# BackplaneConnector.net
KiCad netlist of a schematic drawn in Altium Designer
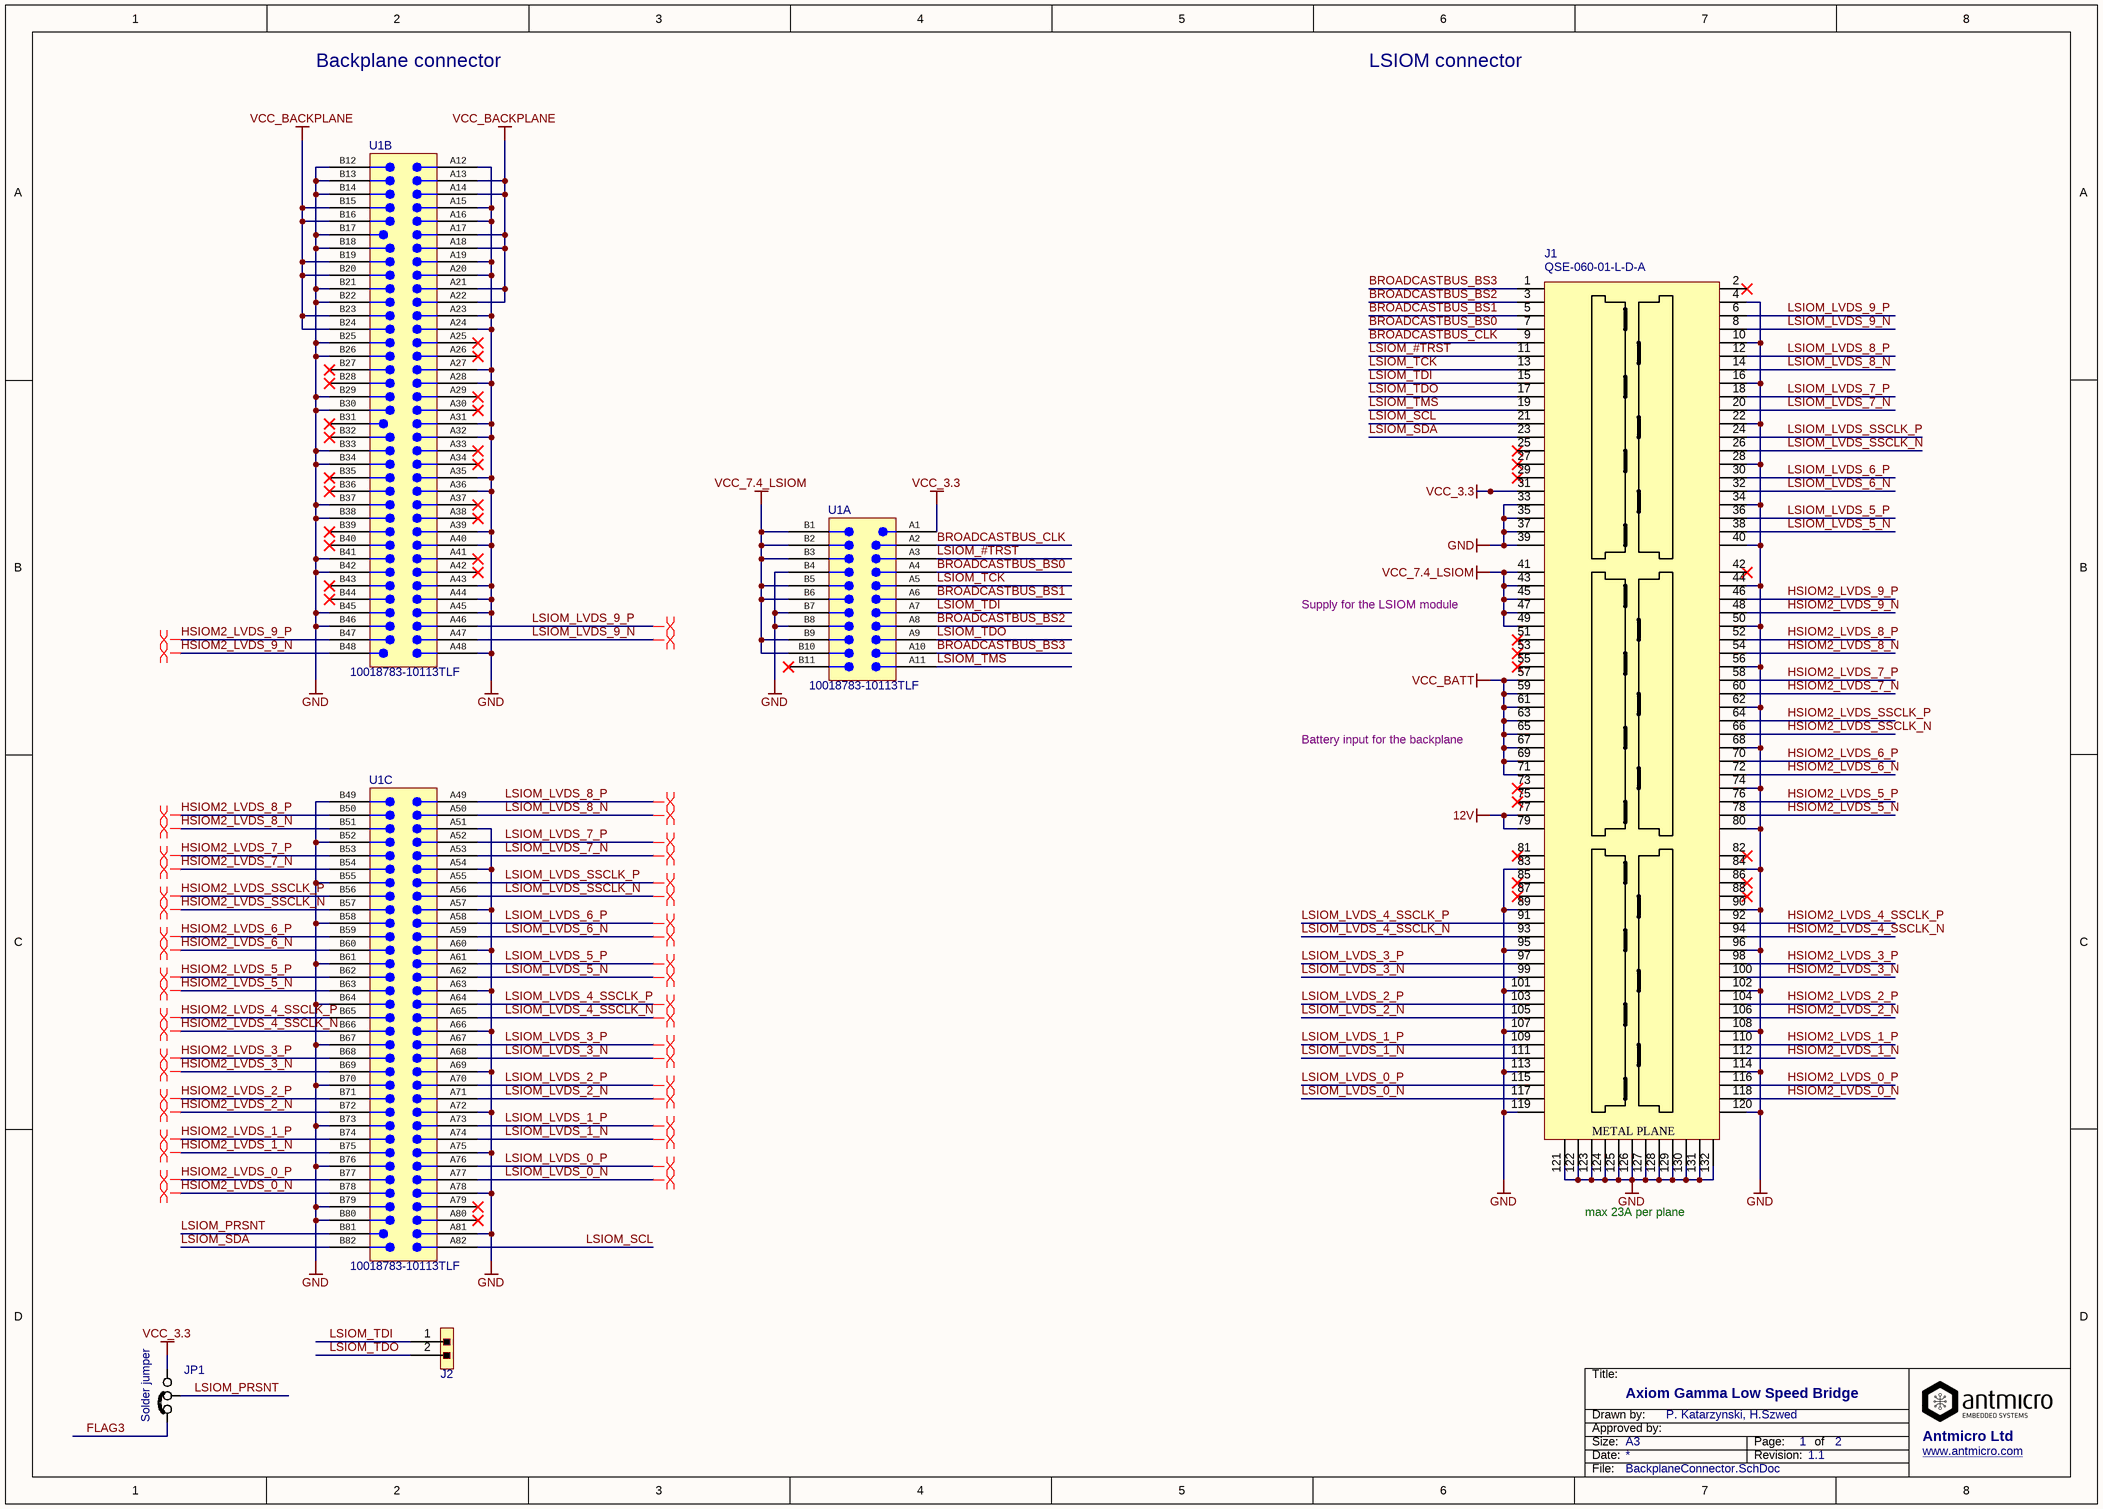
[diagram p0: BackplaneConnector.SchDoc]

(export (version "E")
  (design (tool "Eeschema 10.0.6"))
  (components
    (comp (ref "J1")
      (value "QSE-060-01-L-D-A")
      (footprint "QSE-060-01-L-D-A")
      (fields (field (name "MANUFACTURER") "SAMTEC"))
      (libsource (lib "Axiom_Gamma_LSB") (part "QSE-060-01-L-D-A"))
    )
    (comp (ref "J2")
      (value "1x2 pinhead 2.54mm male")
      (footprint "HEADER_1X2_male 2.54mm Angle")
      (description "1x2 pinhead male angle")
      (fields (field (name "PART NUMBER") "HEADER_1X2_male_angle") (field (name "MANUFACTURER") "MULTICOMP"))
      (libsource (lib "Axiom_Gamma_LSB") (part "HEADER_1X2_male_angle"))
    )
    (comp (ref "JP1")
      (value "Solder jumper")
      (footprint "JUMPER_2WAY")
      (libsource (lib "Axiom_Gamma_LSB") (part "JUMPER_2WAY"))
    )
    (comp (ref "U1")
      (value "10018783-10113TLF")
      (footprint "10018783-10113TLF")
      (description "PCI Express x16 164 2.36 mm")
      (fields (field (name "MANUFACTURER") "AMPHENOL"))
      (libsource (lib "Axiom_Gamma_LSB") (part "10018783-10113TLF"))
    )
  )
  (nets
    (net (code "1") (name "/BROADCASTBUS_BS0") (class "Default")
      (node (ref "J1") (pin "7") (pinfunction "7_7") (pintype "passive"))
      (node (ref "U1") (pin "A4") (pinfunction "A4_A4") (pintype "passive"))
    )
    (net (code "2") (name "/BROADCASTBUS_BS1") (class "Default")
      (node (ref "J1") (pin "5") (pinfunction "5_5") (pintype "passive"))
      (node (ref "U1") (pin "A6") (pinfunction "A6_A6") (pintype "passive"))
    )
    (net (code "3") (name "/BROADCASTBUS_BS2") (class "Default")
      (node (ref "J1") (pin "3") (pinfunction "3_3") (pintype "passive"))
      (node (ref "U1") (pin "A8") (pinfunction "A8_A8") (pintype "passive"))
    )
    (net (code "4") (name "/BROADCASTBUS_BS3") (class "Default")
      (node (ref "J1") (pin "1") (pinfunction "1_1") (pintype "passive"))
      (node (ref "U1") (pin "A10") (pinfunction "A10_A10") (pintype "passive"))
    )
    (net (code "5") (name "/BROADCASTBUS_CLK") (class "Default")
      (node (ref "J1") (pin "9") (pinfunction "9_9") (pintype "passive"))
      (node (ref "U1") (pin "A2") (pinfunction "A2_A2") (pintype "passive"))
    )
    (net (code "6") (name "/FLAG3") (class "Default")
      (node (ref "JP1") (pin "1") (pinfunction "1_1") (pintype "passive"))
    )
    (net (code "7") (name "/HSIOM2_LVDS_0_N") (class "Default")
      (node (ref "J1") (pin "118") (pinfunction "118_118") (pintype "passive"))
      (node (ref "U1") (pin "B78") (pinfunction "B78_B78") (pintype "passive"))
    )
    (net (code "8") (name "/HSIOM2_LVDS_0_P") (class "Default")
      (node (ref "J1") (pin "116") (pinfunction "116_116") (pintype "passive"))
      (node (ref "U1") (pin "B77") (pinfunction "B77_B77") (pintype "passive"))
    )
    (net (code "9") (name "/HSIOM2_LVDS_1_N") (class "Default")
      (node (ref "J1") (pin "112") (pinfunction "112_112") (pintype "passive"))
      (node (ref "U1") (pin "B75") (pinfunction "B75_B75") (pintype "passive"))
    )
    (net (code "10") (name "/HSIOM2_LVDS_1_P") (class "Default")
      (node (ref "J1") (pin "110") (pinfunction "110_110") (pintype "passive"))
      (node (ref "U1") (pin "B74") (pinfunction "B74_B74") (pintype "passive"))
    )
    (net (code "11") (name "/HSIOM2_LVDS_2_N") (class "Default")
      (node (ref "J1") (pin "106") (pinfunction "106_106") (pintype "passive"))
      (node (ref "U1") (pin "B72") (pinfunction "B72_B72") (pintype "passive"))
    )
    (net (code "12") (name "/HSIOM2_LVDS_2_P") (class "Default")
      (node (ref "J1") (pin "104") (pinfunction "104_104") (pintype "passive"))
      (node (ref "U1") (pin "B71") (pinfunction "B71_B71") (pintype "passive"))
    )
    (net (code "13") (name "/HSIOM2_LVDS_3_N") (class "Default")
      (node (ref "J1") (pin "100") (pinfunction "100_100") (pintype "passive"))
      (node (ref "U1") (pin "B69") (pinfunction "B69_B69") (pintype "passive"))
    )
    (net (code "14") (name "/HSIOM2_LVDS_3_P") (class "Default")
      (node (ref "J1") (pin "98") (pinfunction "98_98") (pintype "passive"))
      (node (ref "U1") (pin "B68") (pinfunction "B68_B68") (pintype "passive"))
    )
    (net (code "15") (name "/HSIOM2_LVDS_4_SSCLK_N") (class "Default")
      (node (ref "J1") (pin "94") (pinfunction "94_94") (pintype "passive"))
      (node (ref "U1") (pin "B66") (pinfunction "B66_B66") (pintype "passive"))
    )
    (net (code "16") (name "/HSIOM2_LVDS_4_SSCLK_P") (class "Default")
      (node (ref "J1") (pin "92") (pinfunction "92_92") (pintype "passive"))
      (node (ref "U1") (pin "B65") (pinfunction "B65_B65") (pintype "passive"))
    )
    (net (code "17") (name "/HSIOM2_LVDS_5_N") (class "Default")
      (node (ref "J1") (pin "78") (pinfunction "78_78") (pintype "passive"))
      (node (ref "U1") (pin "B63") (pinfunction "B63_B63") (pintype "passive"))
    )
    (net (code "18") (name "/HSIOM2_LVDS_5_P") (class "Default")
      (node (ref "J1") (pin "76") (pinfunction "76_76") (pintype "passive"))
      (node (ref "U1") (pin "B62") (pinfunction "B62_B62") (pintype "passive"))
    )
    (net (code "19") (name "/HSIOM2_LVDS_6_N") (class "Default")
      (node (ref "J1") (pin "72") (pinfunction "72_72") (pintype "passive"))
      (node (ref "U1") (pin "B60") (pinfunction "B60_B60") (pintype "passive"))
    )
    (net (code "20") (name "/HSIOM2_LVDS_6_P") (class "Default")
      (node (ref "J1") (pin "70") (pinfunction "70_70") (pintype "passive"))
      (node (ref "U1") (pin "B59") (pinfunction "B59_B59") (pintype "passive"))
    )
    (net (code "21") (name "/HSIOM2_LVDS_7_N") (class "Default")
      (node (ref "J1") (pin "60") (pinfunction "60_60") (pintype "passive"))
      (node (ref "U1") (pin "B54") (pinfunction "B54_B54") (pintype "passive"))
    )
    (net (code "22") (name "/HSIOM2_LVDS_7_P") (class "Default")
      (node (ref "J1") (pin "58") (pinfunction "58_58") (pintype "passive"))
      (node (ref "U1") (pin "B53") (pinfunction "B53_B53") (pintype "passive"))
    )
    (net (code "23") (name "/HSIOM2_LVDS_8_N") (class "Default")
      (node (ref "J1") (pin "54") (pinfunction "54_54") (pintype "passive"))
      (node (ref "U1") (pin "B51") (pinfunction "B51_B51") (pintype "passive"))
    )
    (net (code "24") (name "/HSIOM2_LVDS_8_P") (class "Default")
      (node (ref "J1") (pin "52") (pinfunction "52_52") (pintype "passive"))
      (node (ref "U1") (pin "B50") (pinfunction "B50_B50") (pintype "passive"))
    )
    (net (code "25") (name "/HSIOM2_LVDS_9_N") (class "Default")
      (node (ref "J1") (pin "48") (pinfunction "48_48") (pintype "passive"))
      (node (ref "U1") (pin "B48") (pinfunction "B48_B48") (pintype "passive"))
    )
    (net (code "26") (name "/HSIOM2_LVDS_9_P") (class "Default")
      (node (ref "J1") (pin "46") (pinfunction "46_46") (pintype "passive"))
      (node (ref "U1") (pin "B47") (pinfunction "B47_B47") (pintype "passive"))
    )
    (net (code "27") (name "/HSIOM2_LVDS_SSCLK_N") (class "Default")
      (node (ref "J1") (pin "66") (pinfunction "66_66") (pintype "passive"))
      (node (ref "U1") (pin "B57") (pinfunction "B57_B57") (pintype "passive"))
    )
    (net (code "28") (name "/HSIOM2_LVDS_SSCLK_P") (class "Default")
      (node (ref "J1") (pin "64") (pinfunction "64_64") (pintype "passive"))
      (node (ref "U1") (pin "B56") (pinfunction "B56_B56") (pintype "passive"))
    )
    (net (code "29") (name "/LSIOM_#TRST") (class "Default")
      (node (ref "J1") (pin "11") (pinfunction "11_11") (pintype "passive"))
      (node (ref "U1") (pin "A3") (pinfunction "A3_A3") (pintype "passive"))
    )
    (net (code "30") (name "/LSIOM_LVDS_0_N") (class "Default")
      (node (ref "J1") (pin "117") (pinfunction "117_117") (pintype "passive"))
      (node (ref "U1") (pin "A77") (pinfunction "A77_A77") (pintype "passive"))
    )
    (net (code "31") (name "/LSIOM_LVDS_0_P") (class "Default")
      (node (ref "J1") (pin "115") (pinfunction "115_115") (pintype "passive"))
      (node (ref "U1") (pin "A76") (pinfunction "A76_A76") (pintype "passive"))
    )
    (net (code "32") (name "/LSIOM_LVDS_1_N") (class "Default")
      (node (ref "J1") (pin "111") (pinfunction "111_111") (pintype "passive"))
      (node (ref "U1") (pin "A74") (pinfunction "A74_A74") (pintype "passive"))
    )
    (net (code "33") (name "/LSIOM_LVDS_1_P") (class "Default")
      (node (ref "J1") (pin "109") (pinfunction "109_109") (pintype "passive"))
      (node (ref "U1") (pin "A73") (pinfunction "A73_A73") (pintype "passive"))
    )
    (net (code "34") (name "/LSIOM_LVDS_2_N") (class "Default")
      (node (ref "J1") (pin "105") (pinfunction "105_105") (pintype "passive"))
      (node (ref "U1") (pin "A71") (pinfunction "A71_A71") (pintype "passive"))
    )
    (net (code "35") (name "/LSIOM_LVDS_2_P") (class "Default")
      (node (ref "J1") (pin "103") (pinfunction "103_103") (pintype "passive"))
      (node (ref "U1") (pin "A70") (pinfunction "A70_A70") (pintype "passive"))
    )
    (net (code "36") (name "/LSIOM_LVDS_3_N") (class "Default")
      (node (ref "J1") (pin "99") (pinfunction "99_99") (pintype "passive"))
      (node (ref "U1") (pin "A68") (pinfunction "A68_A68") (pintype "passive"))
    )
    (net (code "37") (name "/LSIOM_LVDS_3_P") (class "Default")
      (node (ref "J1") (pin "97") (pinfunction "97_97") (pintype "passive"))
      (node (ref "U1") (pin "A67") (pinfunction "A67_A67") (pintype "passive"))
    )
    (net (code "38") (name "/LSIOM_LVDS_4_SSCLK_N") (class "Default")
      (node (ref "J1") (pin "93") (pinfunction "93_93") (pintype "passive"))
      (node (ref "U1") (pin "A65") (pinfunction "A65_A65") (pintype "passive"))
    )
    (net (code "39") (name "/LSIOM_LVDS_4_SSCLK_P") (class "Default")
      (node (ref "J1") (pin "91") (pinfunction "91_91") (pintype "passive"))
      (node (ref "U1") (pin "A64") (pinfunction "A64_A64") (pintype "passive"))
    )
    (net (code "40") (name "/LSIOM_LVDS_5_N") (class "Default")
      (node (ref "J1") (pin "38") (pinfunction "38_38") (pintype "passive"))
      (node (ref "U1") (pin "A62") (pinfunction "A62_A62") (pintype "passive"))
    )
    (net (code "41") (name "/LSIOM_LVDS_5_P") (class "Default")
      (node (ref "J1") (pin "36") (pinfunction "36_36") (pintype "passive"))
      (node (ref "U1") (pin "A61") (pinfunction "A61_A61") (pintype "passive"))
    )
    (net (code "42") (name "/LSIOM_LVDS_6_N") (class "Default")
      (node (ref "J1") (pin "32") (pinfunction "32_32") (pintype "passive"))
      (node (ref "U1") (pin "A59") (pinfunction "A59_A59") (pintype "passive"))
    )
    (net (code "43") (name "/LSIOM_LVDS_6_P") (class "Default")
      (node (ref "J1") (pin "30") (pinfunction "30_30") (pintype "passive"))
      (node (ref "U1") (pin "A58") (pinfunction "A58_A58") (pintype "passive"))
    )
    (net (code "44") (name "/LSIOM_LVDS_7_N") (class "Default")
      (node (ref "J1") (pin "20") (pinfunction "20_20") (pintype "passive"))
      (node (ref "U1") (pin "A53") (pinfunction "A53_A53") (pintype "passive"))
    )
    (net (code "45") (name "/LSIOM_LVDS_7_P") (class "Default")
      (node (ref "J1") (pin "18") (pinfunction "18_18") (pintype "passive"))
      (node (ref "U1") (pin "A52") (pinfunction "A52_A52") (pintype "passive"))
    )
    (net (code "46") (name "/LSIOM_LVDS_8_N") (class "Default")
      (node (ref "J1") (pin "14") (pinfunction "14_14") (pintype "passive"))
      (node (ref "U1") (pin "A50") (pinfunction "A50_A50") (pintype "passive"))
    )
    (net (code "47") (name "/LSIOM_LVDS_8_P") (class "Default")
      (node (ref "J1") (pin "12") (pinfunction "12_12") (pintype "passive"))
      (node (ref "U1") (pin "A49") (pinfunction "A49_A49") (pintype "passive"))
    )
    (net (code "48") (name "/LSIOM_LVDS_9_N") (class "Default")
      (node (ref "J1") (pin "8") (pinfunction "8_8") (pintype "passive"))
      (node (ref "U1") (pin "A47") (pinfunction "A47_A47") (pintype "passive"))
    )
    (net (code "49") (name "/LSIOM_LVDS_9_P") (class "Default")
      (node (ref "J1") (pin "6") (pinfunction "6_6") (pintype "passive"))
      (node (ref "U1") (pin "A46") (pinfunction "A46_A46") (pintype "passive"))
    )
    (net (code "50") (name "/LSIOM_LVDS_SSCLK_N") (class "Default")
      (node (ref "J1") (pin "26") (pinfunction "26_26") (pintype "passive"))
      (node (ref "U1") (pin "A56") (pinfunction "A56_A56") (pintype "passive"))
    )
    (net (code "51") (name "/LSIOM_LVDS_SSCLK_P") (class "Default")
      (node (ref "J1") (pin "24") (pinfunction "24_24") (pintype "passive"))
      (node (ref "U1") (pin "A55") (pinfunction "A55_A55") (pintype "passive"))
    )
    (net (code "52") (name "/LSIOM_PRSNT") (class "Default")
      (node (ref "JP1") (pin "2") (pinfunction "2_2") (pintype "passive"))
      (node (ref "U1") (pin "B81") (pinfunction "B81_B81") (pintype "passive"))
    )
    (net (code "53") (name "/LSIOM_SCL") (class "Default")
      (node (ref "J1") (pin "21") (pinfunction "21_21") (pintype "passive"))
      (node (ref "U1") (pin "A82") (pinfunction "A82_A82") (pintype "passive"))
    )
    (net (code "54") (name "/LSIOM_SDA") (class "Default")
      (node (ref "J1") (pin "23") (pinfunction "23_23") (pintype "passive"))
      (node (ref "U1") (pin "B82") (pinfunction "B82_B82") (pintype "passive"))
    )
    (net (code "55") (name "/LSIOM_TCK") (class "Default")
      (node (ref "J1") (pin "13") (pinfunction "13_13") (pintype "passive"))
      (node (ref "U1") (pin "A5") (pinfunction "A5_A5") (pintype "passive"))
    )
    (net (code "56") (name "/LSIOM_TDI") (class "Default")
      (node (ref "J1") (pin "15") (pinfunction "15_15") (pintype "passive"))
      (node (ref "J2") (pin "1") (pinfunction "1_1") (pintype "passive"))
      (node (ref "U1") (pin "A7") (pinfunction "A7_A7") (pintype "passive"))
    )
    (net (code "57") (name "/LSIOM_TDO") (class "Default")
      (node (ref "J1") (pin "17") (pinfunction "17_17") (pintype "passive"))
      (node (ref "J2") (pin "2") (pinfunction "2_2") (pintype "passive"))
      (node (ref "U1") (pin "A9") (pinfunction "A9_A9") (pintype "passive"))
    )
    (net (code "58") (name "/LSIOM_TMS") (class "Default")
      (node (ref "J1") (pin "19") (pinfunction "19_19") (pintype "passive"))
      (node (ref "U1") (pin "A11") (pinfunction "A11_A11") (pintype "passive"))
    )
    (net (code "59") (name "12V") (class "Default")
      (node (ref "J1") (pin "77") (pinfunction "77_77") (pintype "passive"))
      (node (ref "J1") (pin "79") (pinfunction "79_79") (pintype "passive"))
    )
    (net (code "60") (name "GND") (class "Default")
      (node (ref "J1") (pin "10") (pinfunction "10_10") (pintype "passive"))
      (node (ref "J1") (pin "101") (pinfunction "101_101") (pintype "passive"))
      (node (ref "J1") (pin "102") (pinfunction "102_102") (pintype "passive"))
      (node (ref "J1") (pin "107") (pinfunction "107_107") (pintype "passive"))
      (node (ref "J1") (pin "108") (pinfunction "108_108") (pintype "passive"))
      (node (ref "J1") (pin "113") (pinfunction "113_113") (pintype "passive"))
      (node (ref "J1") (pin "114") (pinfunction "114_114") (pintype "passive"))
      (node (ref "J1") (pin "119") (pinfunction "119_119") (pintype "passive"))
      (node (ref "J1") (pin "120") (pinfunction "120_120") (pintype "passive"))
      (node (ref "J1") (pin "121") (pinfunction "121_121") (pintype "passive"))
      (node (ref "J1") (pin "122") (pinfunction "122_122") (pintype "passive"))
      (node (ref "J1") (pin "123") (pinfunction "123_123") (pintype "passive"))
      (node (ref "J1") (pin "124") (pinfunction "124_124") (pintype "passive"))
      (node (ref "J1") (pin "125") (pinfunction "125_125") (pintype "passive"))
      (node (ref "J1") (pin "126") (pinfunction "126_126") (pintype "passive"))
      (node (ref "J1") (pin "127") (pinfunction "127_127") (pintype "passive"))
      (node (ref "J1") (pin "128") (pinfunction "128_128") (pintype "passive"))
      (node (ref "J1") (pin "129") (pinfunction "129_129") (pintype "passive"))
      (node (ref "J1") (pin "130") (pinfunction "130_130") (pintype "passive"))
      (node (ref "J1") (pin "131") (pinfunction "131_131") (pintype "passive"))
      (node (ref "J1") (pin "132") (pinfunction "132_132") (pintype "passive"))
      (node (ref "J1") (pin "16") (pinfunction "16_16") (pintype "passive"))
      (node (ref "J1") (pin "22") (pinfunction "22_22") (pintype "passive"))
      (node (ref "J1") (pin "28") (pinfunction "28_28") (pintype "passive"))
      (node (ref "J1") (pin "33") (pinfunction "33_33") (pintype "passive"))
      (node (ref "J1") (pin "34") (pinfunction "34_34") (pintype "passive"))
      (node (ref "J1") (pin "35") (pinfunction "35_35") (pintype "passive"))
      (node (ref "J1") (pin "37") (pinfunction "37_37") (pintype "passive"))
      (node (ref "J1") (pin "39") (pinfunction "39_39") (pintype "passive"))
      (node (ref "J1") (pin "4") (pinfunction "4_4") (pintype "passive"))
      (node (ref "J1") (pin "40") (pinfunction "40_40") (pintype "passive"))
      (node (ref "J1") (pin "44") (pinfunction "44_44") (pintype "passive"))
      (node (ref "J1") (pin "50") (pinfunction "50_50") (pintype "passive"))
      (node (ref "J1") (pin "56") (pinfunction "56_56") (pintype "passive"))
      (node (ref "J1") (pin "62") (pinfunction "62_62") (pintype "passive"))
      (node (ref "J1") (pin "68") (pinfunction "68_68") (pintype "passive"))
      (node (ref "J1") (pin "74") (pinfunction "74_74") (pintype "passive"))
      (node (ref "J1") (pin "80") (pinfunction "80_80") (pintype "passive"))
      (node (ref "J1") (pin "83") (pinfunction "83_83") (pintype "passive"))
      (node (ref "J1") (pin "84") (pinfunction "84_84") (pintype "passive"))
      (node (ref "J1") (pin "89") (pinfunction "89_89") (pintype "passive"))
      (node (ref "J1") (pin "90") (pinfunction "90_90") (pintype "passive"))
      (node (ref "J1") (pin "95") (pinfunction "95_95") (pintype "passive"))
      (node (ref "J1") (pin "96") (pinfunction "96_96") (pintype "passive"))
      (node (ref "U1") (pin "A12") (pinfunction "A12_A12") (pintype "passive"))
      (node (ref "U1") (pin "A15") (pinfunction "A15_A15") (pintype "passive"))
      (node (ref "U1") (pin "A16") (pinfunction "A16_A16") (pintype "passive"))
      (node (ref "U1") (pin "A19") (pinfunction "A19_A19") (pintype "passive"))
      (node (ref "U1") (pin "A20") (pinfunction "A20_A20") (pintype "passive"))
      (node (ref "U1") (pin "A23") (pinfunction "A23_A23") (pintype "passive"))
      (node (ref "U1") (pin "A24") (pinfunction "A24_A24") (pintype "passive"))
      (node (ref "U1") (pin "A27") (pinfunction "A27_A27") (pintype "passive"))
      (node (ref "U1") (pin "A28") (pinfunction "A28_A28") (pintype "passive"))
      (node (ref "U1") (pin "A31") (pinfunction "A31_A31") (pintype "passive"))
      (node (ref "U1") (pin "A32") (pinfunction "A32_A32") (pintype "passive"))
      (node (ref "U1") (pin "A35") (pinfunction "A35_A35") (pintype "passive"))
      (node (ref "U1") (pin "A36") (pinfunction "A36_A36") (pintype "passive"))
      (node (ref "U1") (pin "A39") (pinfunction "A39_A39") (pintype "passive"))
      (node (ref "U1") (pin "A40") (pinfunction "A40_A40") (pintype "passive"))
      (node (ref "U1") (pin "A43") (pinfunction "A43_A43") (pintype "passive"))
      (node (ref "U1") (pin "A44") (pinfunction "A44_A44") (pintype "passive"))
      (node (ref "U1") (pin "A45") (pinfunction "A45_A45") (pintype "passive"))
      (node (ref "U1") (pin "A48") (pinfunction "A48_A48") (pintype "passive"))
      (node (ref "U1") (pin "A51") (pinfunction "A51_A51") (pintype "passive"))
      (node (ref "U1") (pin "A54") (pinfunction "A54_A54") (pintype "passive"))
      (node (ref "U1") (pin "A57") (pinfunction "A57_A57") (pintype "passive"))
      (node (ref "U1") (pin "A60") (pinfunction "A60_A60") (pintype "passive"))
      (node (ref "U1") (pin "A63") (pinfunction "A63_A63") (pintype "passive"))
      (node (ref "U1") (pin "A66") (pinfunction "A66_A66") (pintype "passive"))
      (node (ref "U1") (pin "A69") (pinfunction "A69_A69") (pintype "passive"))
      (node (ref "U1") (pin "A72") (pinfunction "A72_A72") (pintype "passive"))
      (node (ref "U1") (pin "A75") (pinfunction "A75_A75") (pintype "passive"))
      (node (ref "U1") (pin "A78") (pinfunction "A78_A78") (pintype "passive"))
      (node (ref "U1") (pin "A81") (pinfunction "A81_A81") (pintype "passive"))
      (node (ref "U1") (pin "B12") (pinfunction "B12_B12") (pintype "passive"))
      (node (ref "U1") (pin "B13") (pinfunction "B13_B13") (pintype "passive"))
      (node (ref "U1") (pin "B14") (pinfunction "B14_B14") (pintype "passive"))
      (node (ref "U1") (pin "B17") (pinfunction "B17_B17") (pintype "passive"))
      (node (ref "U1") (pin "B18") (pinfunction "B18_B18") (pintype "passive"))
      (node (ref "U1") (pin "B21") (pinfunction "B21_B21") (pintype "passive"))
      (node (ref "U1") (pin "B22") (pinfunction "B22_B22") (pintype "passive"))
      (node (ref "U1") (pin "B25") (pinfunction "B25_B25") (pintype "passive"))
      (node (ref "U1") (pin "B26") (pinfunction "B26_B26") (pintype "passive"))
      (node (ref "U1") (pin "B29") (pinfunction "B29_B29") (pintype "passive"))
      (node (ref "U1") (pin "B30") (pinfunction "B30_B30") (pintype "passive"))
      (node (ref "U1") (pin "B33") (pinfunction "B33_B33") (pintype "passive"))
      (node (ref "U1") (pin "B34") (pinfunction "B34_B34") (pintype "passive"))
      (node (ref "U1") (pin "B37") (pinfunction "B37_B37") (pintype "passive"))
      (node (ref "U1") (pin "B38") (pinfunction "B38_B38") (pintype "passive"))
      (node (ref "U1") (pin "B4") (pinfunction "B4_B4") (pintype "passive"))
      (node (ref "U1") (pin "B41") (pinfunction "B41_B41") (pintype "passive"))
      (node (ref "U1") (pin "B42") (pinfunction "B42_B42") (pintype "passive"))
      (node (ref "U1") (pin "B45") (pinfunction "B45_B45") (pintype "passive"))
      (node (ref "U1") (pin "B46") (pinfunction "B46_B46") (pintype "passive"))
      (node (ref "U1") (pin "B49") (pinfunction "B49_B49") (pintype "passive"))
      (node (ref "U1") (pin "B52") (pinfunction "B52_B52") (pintype "passive"))
      (node (ref "U1") (pin "B55") (pinfunction "B55_B55") (pintype "passive"))
      (node (ref "U1") (pin "B58") (pinfunction "B58_B58") (pintype "passive"))
      (node (ref "U1") (pin "B61") (pinfunction "B61_B61") (pintype "passive"))
      (node (ref "U1") (pin "B64") (pinfunction "B64_B64") (pintype "passive"))
      (node (ref "U1") (pin "B67") (pinfunction "B67_B67") (pintype "passive"))
      (node (ref "U1") (pin "B7") (pinfunction "B7_B7") (pintype "passive"))
      (node (ref "U1") (pin "B70") (pinfunction "B70_B70") (pintype "passive"))
      (node (ref "U1") (pin "B73") (pinfunction "B73_B73") (pintype "passive"))
      (node (ref "U1") (pin "B76") (pinfunction "B76_B76") (pintype "passive"))
      (node (ref "U1") (pin "B79") (pinfunction "B79_B79") (pintype "passive"))
      (node (ref "U1") (pin "B8") (pinfunction "B8_B8") (pintype "passive"))
      (node (ref "U1") (pin "B80") (pinfunction "B80_B80") (pintype "passive"))
    )
    (net (code "61") (name "VCC_3.3") (class "Default")
      (node (ref "J1") (pin "31") (pinfunction "31_31") (pintype "passive"))
      (node (ref "JP1") (pin "3") (pinfunction "3_3") (pintype "passive"))
      (node (ref "U1") (pin "A1") (pinfunction "A1_A1") (pintype "passive"))
    )
    (net (code "62") (name "VCC_7.4_LSIOM") (class "Default")
      (node (ref "J1") (pin "41") (pinfunction "41_41") (pintype "passive"))
      (node (ref "J1") (pin "43") (pinfunction "43_43") (pintype "passive"))
      (node (ref "J1") (pin "45") (pinfunction "45_45") (pintype "passive"))
      (node (ref "J1") (pin "47") (pinfunction "47_47") (pintype "passive"))
      (node (ref "J1") (pin "49") (pinfunction "49_49") (pintype "passive"))
      (node (ref "U1") (pin "B1") (pinfunction "B1_B1") (pintype "passive"))
      (node (ref "U1") (pin "B10") (pinfunction "B10_B10") (pintype "passive"))
      (node (ref "U1") (pin "B2") (pinfunction "B2_B2") (pintype "passive"))
      (node (ref "U1") (pin "B3") (pinfunction "B3_B3") (pintype "passive"))
      (node (ref "U1") (pin "B5") (pinfunction "B5_B5") (pintype "passive"))
      (node (ref "U1") (pin "B6") (pinfunction "B6_B6") (pintype "passive"))
      (node (ref "U1") (pin "B9") (pinfunction "B9_B9") (pintype "passive"))
    )
    (net (code "63") (name "VCC_BACKPLANE") (class "Default")
      (node (ref "U1") (pin "A13") (pinfunction "A13_A13") (pintype "passive"))
      (node (ref "U1") (pin "A14") (pinfunction "A14_A14") (pintype "passive"))
      (node (ref "U1") (pin "A17") (pinfunction "A17_A17") (pintype "passive"))
      (node (ref "U1") (pin "A18") (pinfunction "A18_A18") (pintype "passive"))
      (node (ref "U1") (pin "A21") (pinfunction "A21_A21") (pintype "passive"))
      (node (ref "U1") (pin "A22") (pinfunction "A22_A22") (pintype "passive"))
      (node (ref "U1") (pin "B15") (pinfunction "B15_B15") (pintype "passive"))
      (node (ref "U1") (pin "B16") (pinfunction "B16_B16") (pintype "passive"))
      (node (ref "U1") (pin "B19") (pinfunction "B19_B19") (pintype "passive"))
      (node (ref "U1") (pin "B20") (pinfunction "B20_B20") (pintype "passive"))
      (node (ref "U1") (pin "B23") (pinfunction "B23_B23") (pintype "passive"))
      (node (ref "U1") (pin "B24") (pinfunction "B24_B24") (pintype "passive"))
    )
    (net (code "64") (name "VCC_BATT") (class "Default")
      (node (ref "J1") (pin "57") (pinfunction "57_57") (pintype "passive"))
      (node (ref "J1") (pin "59") (pinfunction "59_59") (pintype "passive"))
      (node (ref "J1") (pin "61") (pinfunction "61_61") (pintype "passive"))
      (node (ref "J1") (pin "63") (pinfunction "63_63") (pintype "passive"))
      (node (ref "J1") (pin "65") (pinfunction "65_65") (pintype "passive"))
      (node (ref "J1") (pin "67") (pinfunction "67_67") (pintype "passive"))
      (node (ref "J1") (pin "69") (pinfunction "69_69") (pintype "passive"))
      (node (ref "J1") (pin "71") (pinfunction "71_71") (pintype "passive"))
    )
    (net (code "65") (name "unconnected-(J1-Pad2)") (class "Default")
      (node (ref "J1") (pin "2") (pinfunction "2_2") (pintype "passive+no_connect"))
    )
    (net (code "66") (name "unconnected-(J1-Pad25)") (class "Default")
      (node (ref "J1") (pin "25") (pinfunction "25_25") (pintype "passive+no_connect"))
    )
    (net (code "67") (name "unconnected-(J1-Pad27)") (class "Default")
      (node (ref "J1") (pin "27") (pinfunction "27_27") (pintype "passive+no_connect"))
    )
    (net (code "68") (name "unconnected-(J1-Pad29)") (class "Default")
      (node (ref "J1") (pin "29") (pinfunction "29_29") (pintype "passive+no_connect"))
    )
    (net (code "69") (name "unconnected-(J1-Pad42)") (class "Default")
      (node (ref "J1") (pin "42") (pinfunction "42_42") (pintype "passive+no_connect"))
    )
    (net (code "70") (name "unconnected-(J1-Pad51)") (class "Default")
      (node (ref "J1") (pin "51") (pinfunction "51_51") (pintype "passive+no_connect"))
    )
    (net (code "71") (name "unconnected-(J1-Pad53)") (class "Default")
      (node (ref "J1") (pin "53") (pinfunction "53_53") (pintype "passive+no_connect"))
    )
    (net (code "72") (name "unconnected-(J1-Pad55)") (class "Default")
      (node (ref "J1") (pin "55") (pinfunction "55_55") (pintype "passive+no_connect"))
    )
    (net (code "73") (name "unconnected-(J1-Pad73)") (class "Default")
      (node (ref "J1") (pin "73") (pinfunction "73_73") (pintype "passive+no_connect"))
    )
    (net (code "74") (name "unconnected-(J1-Pad75)") (class "Default")
      (node (ref "J1") (pin "75") (pinfunction "75_75") (pintype "passive+no_connect"))
    )
    (net (code "75") (name "unconnected-(J1-Pad81)") (class "Default")
      (node (ref "J1") (pin "81") (pinfunction "81_81") (pintype "passive+no_connect"))
    )
    (net (code "76") (name "unconnected-(J1-Pad82)") (class "Default")
      (node (ref "J1") (pin "82") (pinfunction "82_82") (pintype "passive+no_connect"))
    )
    (net (code "77") (name "unconnected-(J1-Pad85)") (class "Default")
      (node (ref "J1") (pin "85") (pinfunction "85_85") (pintype "passive+no_connect"))
    )
    (net (code "78") (name "unconnected-(J1-Pad86)") (class "Default")
      (node (ref "J1") (pin "86") (pinfunction "86_86") (pintype "passive+no_connect"))
    )
    (net (code "79") (name "unconnected-(J1-Pad87)") (class "Default")
      (node (ref "J1") (pin "87") (pinfunction "87_87") (pintype "passive+no_connect"))
    )
    (net (code "80") (name "unconnected-(J1-Pad88)") (class "Default")
      (node (ref "J1") (pin "88") (pinfunction "88_88") (pintype "passive+no_connect"))
    )
    (net (code "81") (name "unconnected-(U1-PadA25)") (class "Default")
      (node (ref "U1") (pin "A25") (pinfunction "A25_A25") (pintype "passive+no_connect"))
    )
    (net (code "82") (name "unconnected-(U1-PadA26)") (class "Default")
      (node (ref "U1") (pin "A26") (pinfunction "A26_A26") (pintype "passive+no_connect"))
    )
    (net (code "83") (name "unconnected-(U1-PadA29)") (class "Default")
      (node (ref "U1") (pin "A29") (pinfunction "A29_A29") (pintype "passive+no_connect"))
    )
    (net (code "84") (name "unconnected-(U1-PadA30)") (class "Default")
      (node (ref "U1") (pin "A30") (pinfunction "A30_A30") (pintype "passive+no_connect"))
    )
    (net (code "85") (name "unconnected-(U1-PadA33)") (class "Default")
      (node (ref "U1") (pin "A33") (pinfunction "A33_A33") (pintype "passive+no_connect"))
    )
    (net (code "86") (name "unconnected-(U1-PadA34)") (class "Default")
      (node (ref "U1") (pin "A34") (pinfunction "A34_A34") (pintype "passive+no_connect"))
    )
    (net (code "87") (name "unconnected-(U1-PadA37)") (class "Default")
      (node (ref "U1") (pin "A37") (pinfunction "A37_A37") (pintype "passive+no_connect"))
    )
    (net (code "88") (name "unconnected-(U1-PadA38)") (class "Default")
      (node (ref "U1") (pin "A38") (pinfunction "A38_A38") (pintype "passive+no_connect"))
    )
    (net (code "89") (name "unconnected-(U1-PadA41)") (class "Default")
      (node (ref "U1") (pin "A41") (pinfunction "A41_A41") (pintype "passive+no_connect"))
    )
    (net (code "90") (name "unconnected-(U1-PadA42)") (class "Default")
      (node (ref "U1") (pin "A42") (pinfunction "A42_A42") (pintype "passive+no_connect"))
    )
    (net (code "91") (name "unconnected-(U1-PadA79)") (class "Default")
      (node (ref "U1") (pin "A79") (pinfunction "A79_A79") (pintype "passive+no_connect"))
    )
    (net (code "92") (name "unconnected-(U1-PadA80)") (class "Default")
      (node (ref "U1") (pin "A80") (pinfunction "A80_A80") (pintype "passive+no_connect"))
    )
    (net (code "93") (name "unconnected-(U1-PadB11)") (class "Default")
      (node (ref "U1") (pin "B11") (pinfunction "B11_B11") (pintype "passive+no_connect"))
    )
    (net (code "94") (name "unconnected-(U1-PadB27)") (class "Default")
      (node (ref "U1") (pin "B27") (pinfunction "B27_B27") (pintype "passive+no_connect"))
    )
    (net (code "95") (name "unconnected-(U1-PadB28)") (class "Default")
      (node (ref "U1") (pin "B28") (pinfunction "B28_B28") (pintype "passive+no_connect"))
    )
    (net (code "96") (name "unconnected-(U1-PadB31)") (class "Default")
      (node (ref "U1") (pin "B31") (pinfunction "B31_B31") (pintype "passive+no_connect"))
    )
    (net (code "97") (name "unconnected-(U1-PadB32)") (class "Default")
      (node (ref "U1") (pin "B32") (pinfunction "B32_B32") (pintype "passive+no_connect"))
    )
    (net (code "98") (name "unconnected-(U1-PadB35)") (class "Default")
      (node (ref "U1") (pin "B35") (pinfunction "B35_B35") (pintype "passive+no_connect"))
    )
    (net (code "99") (name "unconnected-(U1-PadB36)") (class "Default")
      (node (ref "U1") (pin "B36") (pinfunction "B36_B36") (pintype "passive+no_connect"))
    )
    (net (code "100") (name "unconnected-(U1-PadB39)") (class "Default")
      (node (ref "U1") (pin "B39") (pinfunction "B39_B39") (pintype "passive+no_connect"))
    )
    (net (code "101") (name "unconnected-(U1-PadB40)") (class "Default")
      (node (ref "U1") (pin "B40") (pinfunction "B40_B40") (pintype "passive+no_connect"))
    )
    (net (code "102") (name "unconnected-(U1-PadB43)") (class "Default")
      (node (ref "U1") (pin "B43") (pinfunction "B43_B43") (pintype "passive+no_connect"))
    )
    (net (code "103") (name "unconnected-(U1-PadB44)") (class "Default")
      (node (ref "U1") (pin "B44") (pinfunction "B44_B44") (pintype "passive+no_connect"))
    )
  )
)
